# Stenophone-Breakout.net
KiCad netlist of a schematic drawn in EAGLE
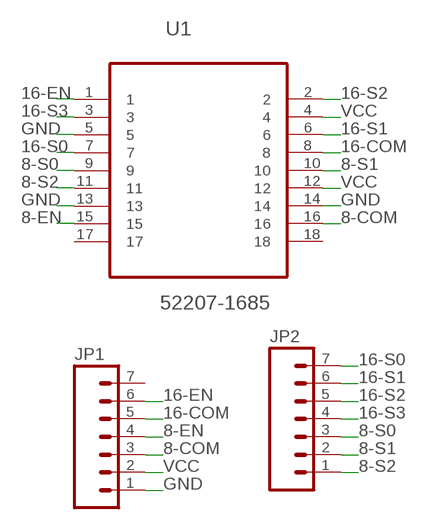
[diagram p0: schematic, sheet 1]

(export (version "E")
  (design (tool "Eeschema 10.0.6"))
  (components
    (comp (ref "JP1")
      (value "M07")
      (footprint "eagle-import:1X07")
      (libsource (lib "eagle-import") (part "M07"))
    )
    (comp (ref "JP2")
      (value "M07")
      (footprint "eagle-import:1X07")
      (libsource (lib "eagle-import") (part "M07"))
    )
    (comp (ref "U1")
      (value "52207-1685")
      (footprint "eagle-import:MOLEX_52207-1685")
      (libsource (lib "eagle-import") (part "52207-1685"))
    )
  )
  (nets
    (net (code "1") (name "/8-COM") (class "Default")
      (node (ref "JP1") (pin "3") (pinfunction "3_3") (pintype "passive"))
      (node (ref "U1") (pin "16") (pinfunction "16_16") (pintype "passive"))
    )
    (net (code "2") (name "/8-EN") (class "Default")
      (node (ref "JP1") (pin "4") (pinfunction "4_4") (pintype "passive"))
      (node (ref "U1") (pin "15") (pinfunction "15_15") (pintype "passive"))
    )
    (net (code "3") (name "/8-S0") (class "Default")
      (node (ref "JP2") (pin "3") (pinfunction "3_3") (pintype "passive"))
      (node (ref "U1") (pin "9") (pinfunction "9_9") (pintype "passive"))
    )
    (net (code "4") (name "/8-S1") (class "Default")
      (node (ref "JP2") (pin "2") (pinfunction "2_2") (pintype "passive"))
      (node (ref "U1") (pin "10") (pinfunction "10_10") (pintype "passive"))
    )
    (net (code "5") (name "/8-S2") (class "Default")
      (node (ref "JP2") (pin "1") (pinfunction "1_1") (pintype "passive"))
      (node (ref "U1") (pin "11") (pinfunction "11_11") (pintype "passive"))
    )
    (net (code "6") (name "/16-COM") (class "Default")
      (node (ref "JP1") (pin "5") (pinfunction "5_5") (pintype "passive"))
      (node (ref "U1") (pin "8") (pinfunction "8_8") (pintype "passive"))
    )
    (net (code "7") (name "/16-EN") (class "Default")
      (node (ref "JP1") (pin "6") (pinfunction "6_6") (pintype "passive"))
      (node (ref "U1") (pin "1") (pinfunction "1_1") (pintype "passive"))
    )
    (net (code "8") (name "/16-S0") (class "Default")
      (node (ref "JP2") (pin "7") (pinfunction "7_7") (pintype "passive"))
      (node (ref "U1") (pin "7") (pinfunction "7_7") (pintype "passive"))
    )
    (net (code "9") (name "/16-S1") (class "Default")
      (node (ref "JP2") (pin "6") (pinfunction "6_6") (pintype "passive"))
      (node (ref "U1") (pin "6") (pinfunction "6_6") (pintype "passive"))
    )
    (net (code "10") (name "/16-S2") (class "Default")
      (node (ref "JP2") (pin "5") (pinfunction "5_5") (pintype "passive"))
      (node (ref "U1") (pin "2") (pinfunction "2_2") (pintype "passive"))
    )
    (net (code "11") (name "/16-S3") (class "Default")
      (node (ref "JP2") (pin "4") (pinfunction "4_4") (pintype "passive"))
      (node (ref "U1") (pin "3") (pinfunction "3_3") (pintype "passive"))
    )
    (net (code "12") (name "/GND") (class "Default")
      (node (ref "JP1") (pin "1") (pinfunction "1_1") (pintype "passive"))
      (node (ref "U1") (pin "13") (pinfunction "13_13") (pintype "passive"))
      (node (ref "U1") (pin "14") (pinfunction "14_14") (pintype "passive"))
      (node (ref "U1") (pin "5") (pinfunction "5_5") (pintype "passive"))
    )
    (net (code "13") (name "/VCC") (class "Default")
      (node (ref "JP1") (pin "2") (pinfunction "2_2") (pintype "passive"))
      (node (ref "U1") (pin "12") (pinfunction "12_12") (pintype "passive"))
      (node (ref "U1") (pin "4") (pinfunction "4_4") (pintype "passive"))
    )
    (net (code "14") (name "unconnected-(JP1-Pad7)") (class "Default")
      (node (ref "JP1") (pin "7") (pinfunction "7_7") (pintype "passive"))
    )
    (net (code "15") (name "unconnected-(U1-Pad17)") (class "Default")
      (node (ref "U1") (pin "17") (pinfunction "17_17") (pintype "passive"))
    )
    (net (code "16") (name "unconnected-(U1-Pad18)") (class "Default")
      (node (ref "U1") (pin "18") (pinfunction "18_18") (pintype "passive"))
    )
  )
)
